# ModuleCarrier-Murata-ABZ-v1_0_0.net
KiCad netlist of a schematic drawn in EAGLE
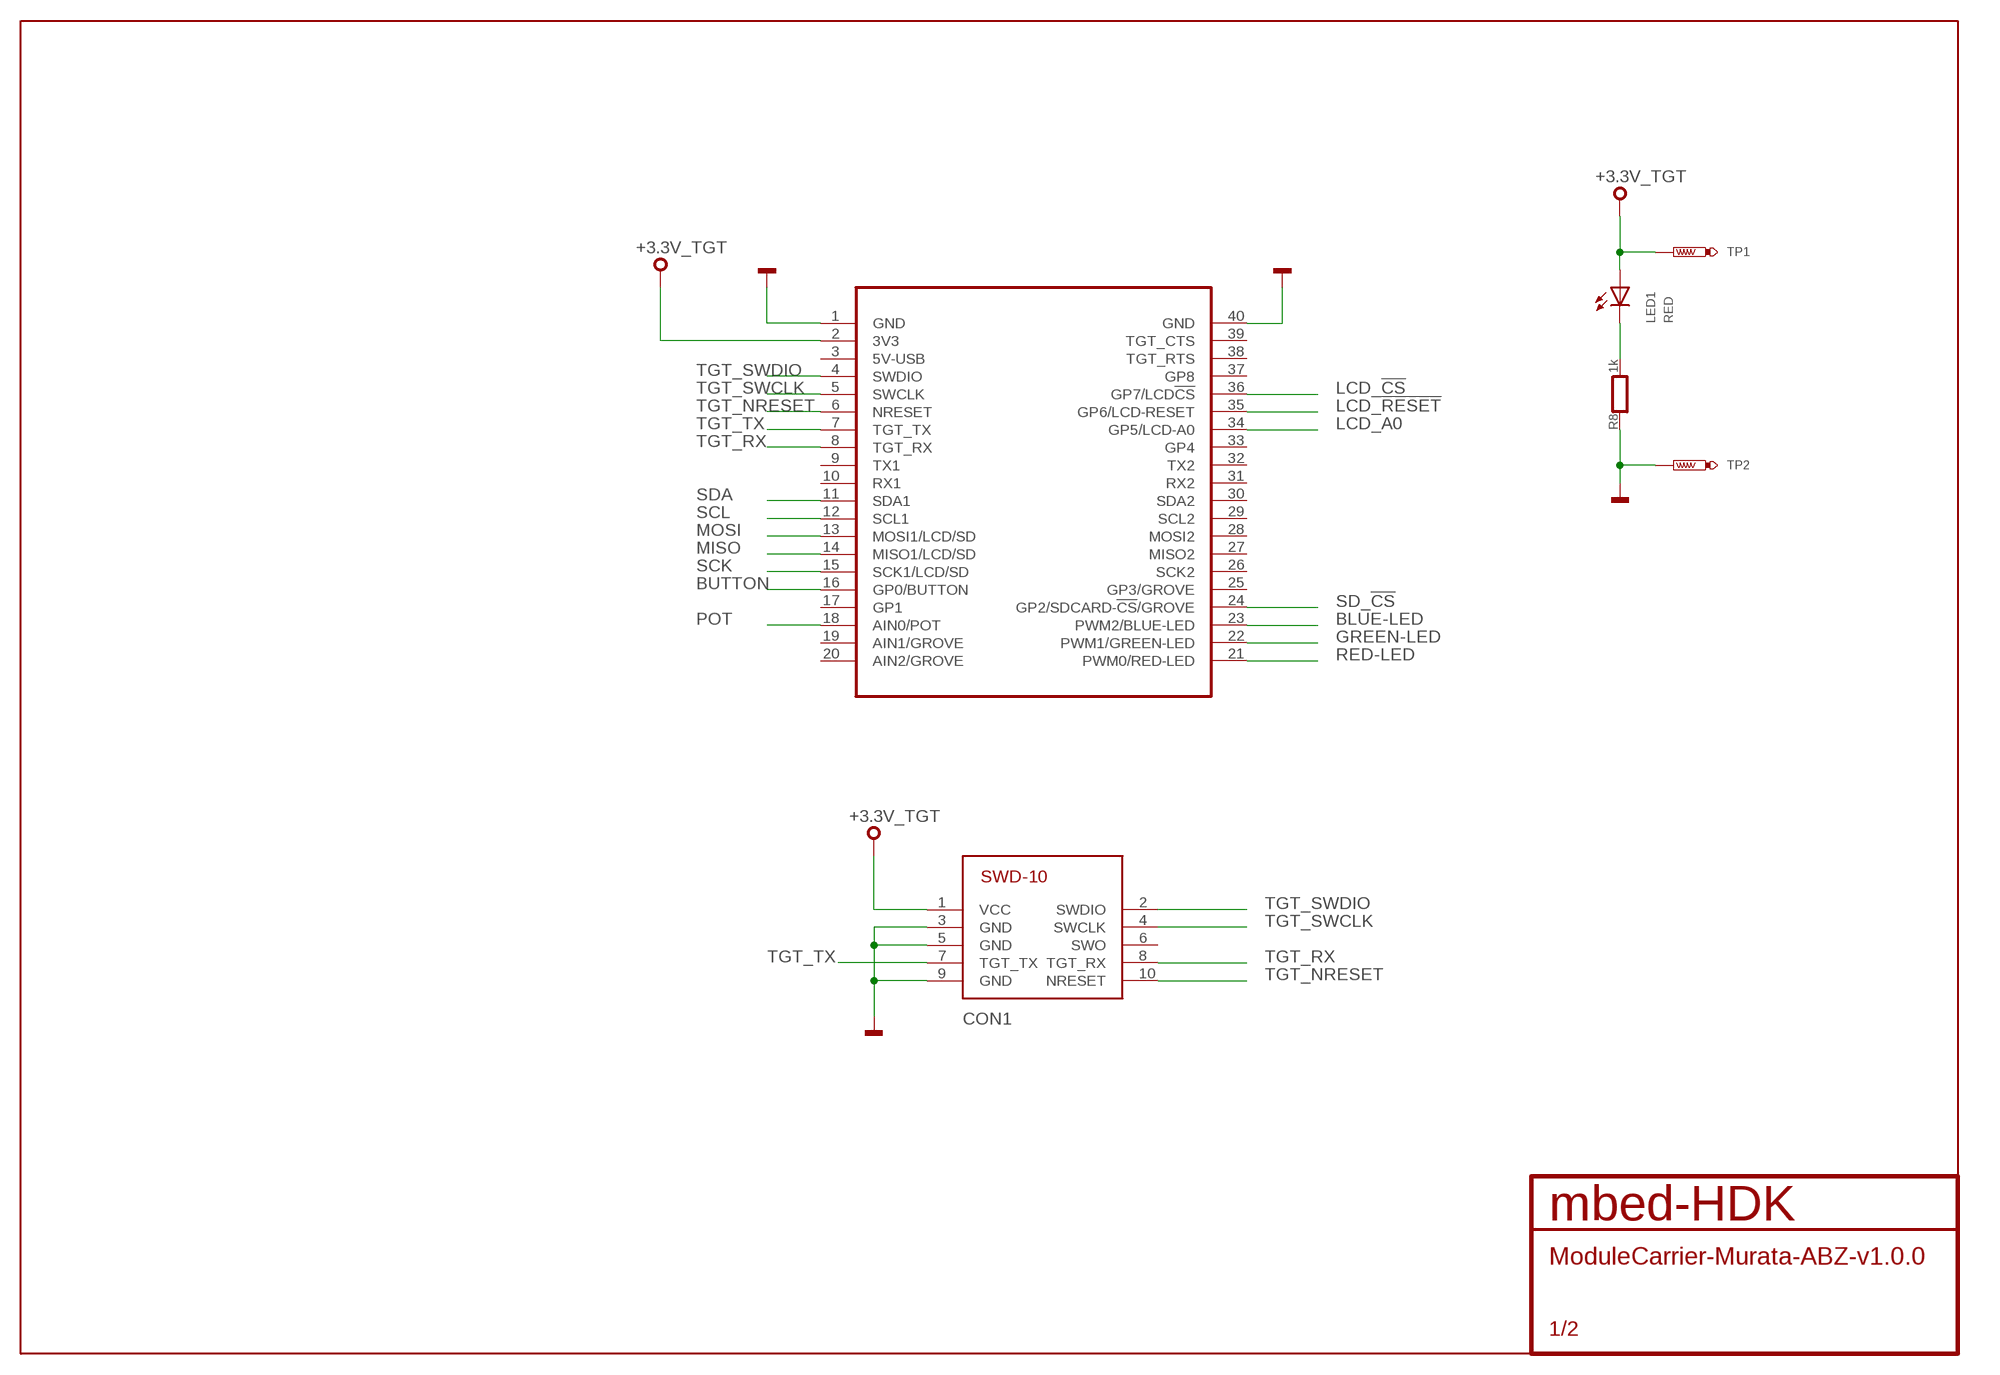
[diagram p0: schematic, sheet 1]
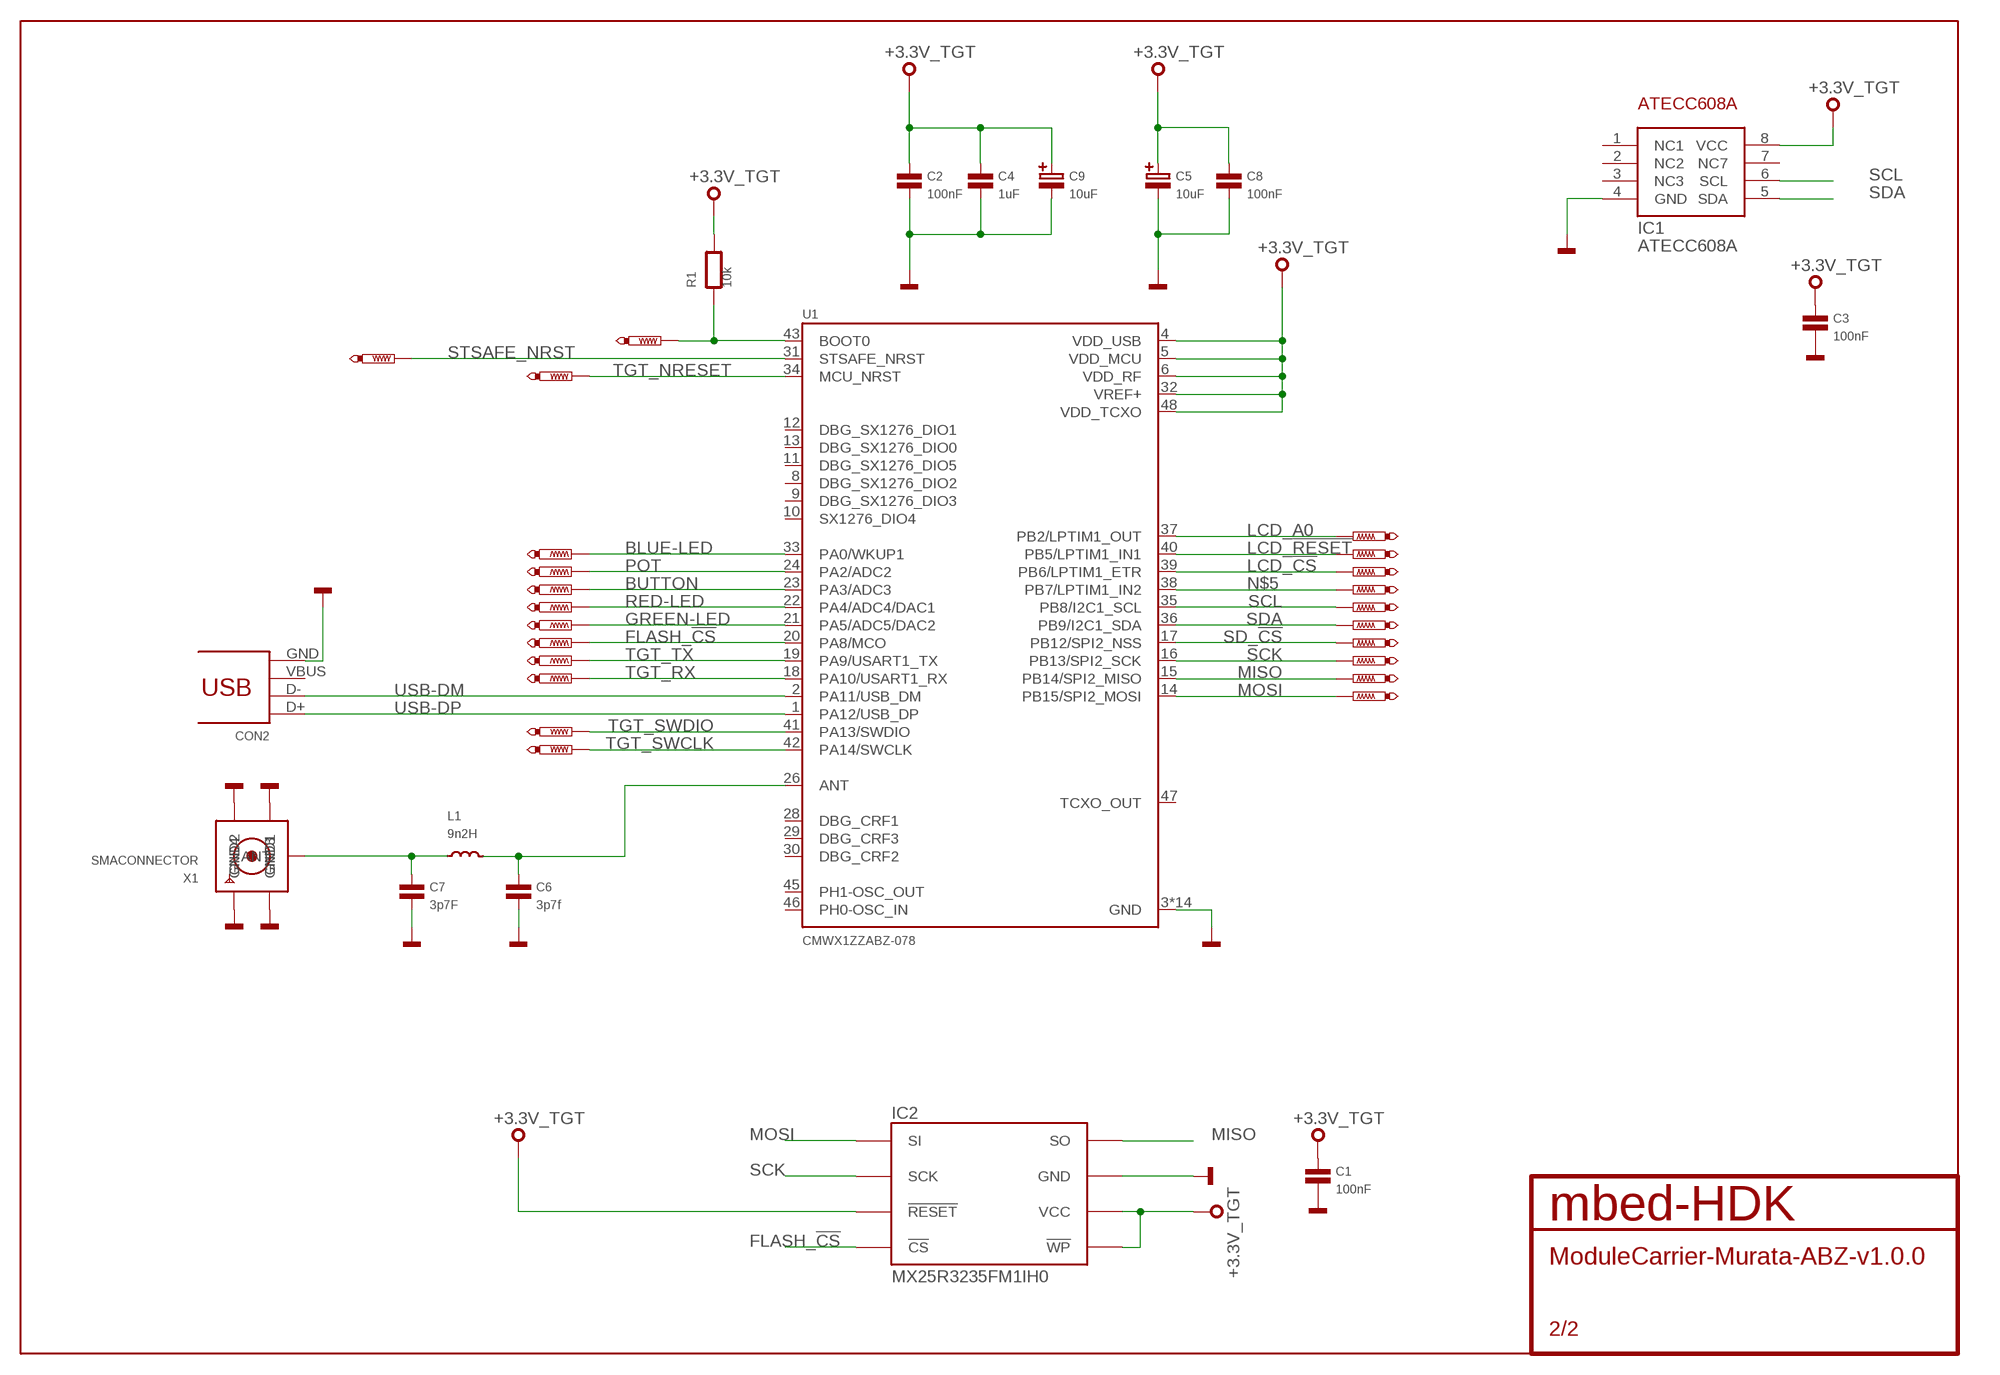
[diagram p1: schematic, sheet 2]

(export (version "E")
  (design (tool "Eeschema 10.0.6"))
  (components
    (comp (ref "C1")
      (value "100nF")
      (footprint "eagle-import:0603")
      (libsource (lib "eagle-import") (part "CAPACITOR0603"))
    )
    (comp (ref "C2")
      (value "100nF")
      (footprint "eagle-import:0603")
      (libsource (lib "eagle-import") (part "CAPACITOR0603"))
    )
    (comp (ref "C3")
      (value "100nF")
      (footprint "eagle-import:0603")
      (libsource (lib "eagle-import") (part "CAPACITOR0603"))
    )
    (comp (ref "C4")
      (value "1uF")
      (footprint "eagle-import:0603")
      (libsource (lib "eagle-import") (part "CAPACITOR0603"))
    )
    (comp (ref "C5")
      (value "10uF")
      (footprint "eagle-import:SMC_B")
      (fields (field (name "MF") "Kemet"))
      (libsource (lib "eagle-import") (part "CAPACITOR-POLARISEDB"))
    )
    (comp (ref "C6")
      (value "3p7f")
      (footprint "eagle-import:0603")
      (libsource (lib "eagle-import") (part "CAPACITOR0603"))
    )
    (comp (ref "C7")
      (value "3p7F")
      (footprint "eagle-import:0603")
      (libsource (lib "eagle-import") (part "CAPACITOR0603"))
    )
    (comp (ref "C8")
      (value "100nF")
      (footprint "eagle-import:0603")
      (libsource (lib "eagle-import") (part "CAPACITOR0603"))
    )
    (comp (ref "C9")
      (value "10uF")
      (footprint "eagle-import:SMC_B")
      (fields (field (name "MF") "Kemet"))
      (libsource (lib "eagle-import") (part "CAPACITOR-POLARISEDB"))
    )
    (comp (ref "CON2")
      (value "10033526-N3212MLF")
      (footprint "eagle-import:USB-MINI-B-H")
      (fields (field (name "MF") "Amphenol FCI"))
      (libsource (lib "eagle-import") (part "10033526-N3212MLF"))
    )
    (comp (ref "IC1")
      (value "ATECC608A")
      (footprint "eagle-import:SO8")
      (libsource (lib "eagle-import") (part "ATECC608A"))
    )
    (comp (ref "IC2")
      (value "MX25R3235FM1IH0")
      (footprint "eagle-import:SO8")
      (fields (field (name "MF") "Macronix"))
      (libsource (lib "eagle-import") (part "MX25R3235FM1IH0"))
    )
    (comp (ref "L1")
      (value "9n2H")
      (footprint "eagle-import:0603")
      (libsource (lib "eagle-import") (part "INDUCTOR0603"))
    )
    (comp (ref "R1")
      (value "10k")
      (footprint "eagle-import:0603")
      (libsource (lib "eagle-import") (part "RESISTOR0603"))
    )
    (comp (ref "TP3")
      (value "PTR1TP08R")
      (footprint "eagle-import:TP08R")
      (libsource (lib "eagle-import") (part "PTR1TP08R"))
    )
    (comp (ref "TP4")
      (value "PTR1TP08R")
      (footprint "eagle-import:TP08R")
      (libsource (lib "eagle-import") (part "PTR1TP08R"))
    )
    (comp (ref "TP5")
      (value "PTR1TP08R")
      (footprint "eagle-import:TP08R")
      (libsource (lib "eagle-import") (part "PTR1TP08R"))
    )
    (comp (ref "TP6")
      (value "PTR1TP08R")
      (footprint "eagle-import:TP08R")
      (libsource (lib "eagle-import") (part "PTR1TP08R"))
    )
    (comp (ref "TP7")
      (value "PTR1TP08R")
      (footprint "eagle-import:TP08R")
      (libsource (lib "eagle-import") (part "PTR1TP08R"))
    )
    (comp (ref "TP8")
      (value "PTR1TP08R")
      (footprint "eagle-import:TP08R")
      (libsource (lib "eagle-import") (part "PTR1TP08R"))
    )
    (comp (ref "TP9")
      (value "PTR1TP08R")
      (footprint "eagle-import:TP08R")
      (libsource (lib "eagle-import") (part "PTR1TP08R"))
    )
    (comp (ref "TP10")
      (value "PTR1TP08R")
      (footprint "eagle-import:TP08R")
      (libsource (lib "eagle-import") (part "PTR1TP08R"))
    )
    (comp (ref "TP11")
      (value "PTR1TP08R")
      (footprint "eagle-import:TP08R")
      (libsource (lib "eagle-import") (part "PTR1TP08R"))
    )
    (comp (ref "TP12")
      (value "PTR1TP08R")
      (footprint "eagle-import:TP08R")
      (libsource (lib "eagle-import") (part "PTR1TP08R"))
    )
    (comp (ref "TP13")
      (value "PTR1TP08R")
      (footprint "eagle-import:TP08R")
      (libsource (lib "eagle-import") (part "PTR1TP08R"))
    )
    (comp (ref "TP14")
      (value "PTR1TP08R")
      (footprint "eagle-import:TP08R")
      (libsource (lib "eagle-import") (part "PTR1TP08R"))
    )
    (comp (ref "TP15")
      (value "PTR1TP08R")
      (footprint "eagle-import:TP08R")
      (libsource (lib "eagle-import") (part "PTR1TP08R"))
    )
    (comp (ref "TP21")
      (value "PTR1TP08R")
      (footprint "eagle-import:TP08R")
      (libsource (lib "eagle-import") (part "PTR1TP08R"))
    )
    (comp (ref "TP22")
      (value "PTR1TP08R")
      (footprint "eagle-import:TP08R")
      (libsource (lib "eagle-import") (part "PTR1TP08R"))
    )
    (comp (ref "TP23")
      (value "PTR1TP08R")
      (footprint "eagle-import:TP08R")
      (libsource (lib "eagle-import") (part "PTR1TP08R"))
    )
    (comp (ref "TP24")
      (value "PTR1TP08R")
      (footprint "eagle-import:TP08R")
      (libsource (lib "eagle-import") (part "PTR1TP08R"))
    )
    (comp (ref "TP25")
      (value "PTR1TP08R")
      (footprint "eagle-import:TP08R")
      (libsource (lib "eagle-import") (part "PTR1TP08R"))
    )
    (comp (ref "TP26")
      (value "PTR1TP08R")
      (footprint "eagle-import:TP08R")
      (libsource (lib "eagle-import") (part "PTR1TP08R"))
    )
    (comp (ref "TP27")
      (value "PTR1TP08R")
      (footprint "eagle-import:TP08R")
      (libsource (lib "eagle-import") (part "PTR1TP08R"))
    )
    (comp (ref "TP28")
      (value "PTR1TP08R")
      (footprint "eagle-import:TP08R")
      (libsource (lib "eagle-import") (part "PTR1TP08R"))
    )
    (comp (ref "TP29")
      (value "PTR1TP08R")
      (footprint "eagle-import:TP08R")
      (libsource (lib "eagle-import") (part "PTR1TP08R"))
    )
    (comp (ref "TP30")
      (value "PTR1TP08R")
      (footprint "eagle-import:TP08R")
      (libsource (lib "eagle-import") (part "PTR1TP08R"))
    )
    (comp (ref "U1")
      (value "CMWX1ZZABZ-078")
      (footprint "eagle-import:XCVR_CMWX1ZZABZ-078")
      (fields (field (name "MF") "Murata"))
      (libsource (lib "eagle-import") (part "CMWX1ZZABZ-078"))
    )
    (comp (ref "X1")
      (value "SMACONNECTOR")
      (footprint "eagle-import:SMA90_DIP")
      (fields (field (name "MF") "LPRS") (field (name "MP") "SMA CONNECTOR"))
      (libsource (lib "eagle-import") (part "SMACONNECTOR"))
    )
    (comp (ref "CON1")
      (value "SWD-10/TC2050_SMD")
      (footprint "eagle-import:FTSH-105-02")
      (libsource (lib "eagle-import") (part "SWD-10/TC2050_SMD"))
    )
    (comp (ref "LED1")
      (value "RED")
      (footprint "eagle-import:CHIPLED_0603")
      (fields (field (name "MF") "Wurth Electronics Inc"))
      (libsource (lib "eagle-import") (part "SMD_LED0603"))
    )
    (comp (ref "MOD1")
      (value "MODULE_DAUGHTER")
      (footprint "eagle-import:MODULE_DAUGHTER")
      (libsource (lib "eagle-import") (part "MODULE_DAUGHTER"))
    )
    (comp (ref "R8")
      (value "1k")
      (footprint "eagle-import:0603")
      (libsource (lib "eagle-import") (part "RESISTOR0603"))
    )
    (comp (ref "TP1")
      (value "TEST-POINT-50R-PTH")
      (footprint "eagle-import:TP50-PTH")
      (libsource (lib "eagle-import") (part "TEST-POINT-50R-PTH"))
    )
    (comp (ref "TP2")
      (value "TEST-POINT-50R-PTH")
      (footprint "eagle-import:TP50-PTH")
      (libsource (lib "eagle-import") (part "TEST-POINT-50R-PTH"))
    )
  )
  (nets
    (net (code "1") (name "+3.3V_TGT") (class "Default")
      (node (ref "C1") (pin "1") (pinfunction "P$1_1") (pintype "passive"))
      (node (ref "C2") (pin "1") (pinfunction "P$1_1") (pintype "passive"))
      (node (ref "C3") (pin "1") (pinfunction "P$1_1") (pintype "passive"))
      (node (ref "C4") (pin "1") (pinfunction "P$1_1") (pintype "passive"))
      (node (ref "C5") (pin "+") (pinfunction "+_+") (pintype "passive"))
      (node (ref "C8") (pin "1") (pinfunction "P$1_1") (pintype "passive"))
      (node (ref "C9") (pin "+") (pinfunction "+_+") (pintype "passive"))
      (node (ref "CON1") (pin "1") (pinfunction "VCC_1") (pintype "bidirectional"))
      (node (ref "IC1") (pin "8") (pinfunction "VCC_8") (pintype "bidirectional"))
      (node (ref "IC2") (pin "3") (pinfunction "~{WP}_3") (pintype "bidirectional"))
      (node (ref "IC2") (pin "7") (pinfunction "~{RESET}_7") (pintype "bidirectional"))
      (node (ref "IC2") (pin "8") (pinfunction "VCC_8") (pintype "bidirectional"))
      (node (ref "LED1") (pin "A") (pinfunction "A_A") (pintype "passive"))
      (node (ref "MOD1") (pin "2") (pinfunction "3V3_2") (pintype "bidirectional"))
      (node (ref "R1") (pin "2") (pinfunction "P$2_2") (pintype "passive"))
      (node (ref "TP1") (pin "TP") (pinfunction "TP_TP") (pintype "input"))
      (node (ref "U1") (pin "32") (pinfunction "VREF+_32") (pintype "power_in"))
      (node (ref "U1") (pin "4") (pinfunction "VDD_USB_4") (pintype "power_in"))
      (node (ref "U1") (pin "48") (pinfunction "VDD_TCXO_48") (pintype "power_in"))
      (node (ref "U1") (pin "5") (pinfunction "VDD_MCU_5") (pintype "power_in"))
      (node (ref "U1") (pin "6") (pinfunction "VDD_RF_6") (pintype "power_in"))
    )
    (net (code "2") (name "BLUE-LED") (class "Default")
      (node (ref "MOD1") (pin "23") (pinfunction "PWM2/BLUE-LED_23") (pintype "bidirectional"))
      (node (ref "TP30") (pin "TP") (pinfunction "TP_TP") (pintype "input"))
      (node (ref "U1") (pin "33") (pinfunction "PA0/WKUP1_33") (pintype "bidirectional"))
    )
    (net (code "3") (name "BUTTON") (class "Default")
      (node (ref "MOD1") (pin "16") (pinfunction "GP0/BUTTON_16") (pintype "bidirectional"))
      (node (ref "TP11") (pin "TP") (pinfunction "TP_TP") (pintype "input"))
      (node (ref "U1") (pin "23") (pinfunction "PA3/ADC3_23") (pintype "bidirectional"))
    )
    (net (code "4") (name "FLASH_~{CS}") (class "Default")
      (node (ref "IC2") (pin "1") (pinfunction "~{CS}_1") (pintype "bidirectional"))
      (node (ref "TP29") (pin "TP") (pinfunction "TP_TP") (pintype "input"))
      (node (ref "U1") (pin "20") (pinfunction "PA8/MCO_20") (pintype "bidirectional"))
    )
    (net (code "5") (name "GND") (class "Default")
      (node (ref "C1") (pin "2") (pinfunction "P$2_2") (pintype "passive"))
      (node (ref "C2") (pin "2") (pinfunction "P$2_2") (pintype "passive"))
      (node (ref "C3") (pin "2") (pinfunction "P$2_2") (pintype "passive"))
      (node (ref "C4") (pin "2") (pinfunction "P$2_2") (pintype "passive"))
      (node (ref "C5") (pin "-") (pinfunction "-_-") (pintype "passive"))
      (node (ref "C6") (pin "2") (pinfunction "P$2_2") (pintype "passive"))
      (node (ref "C7") (pin "2") (pinfunction "P$2_2") (pintype "passive"))
      (node (ref "C8") (pin "2") (pinfunction "P$2_2") (pintype "passive"))
      (node (ref "C9") (pin "-") (pinfunction "-_-") (pintype "passive"))
      (node (ref "CON1") (pin "3") (pinfunction "GND_3") (pintype "bidirectional"))
      (node (ref "CON1") (pin "5") (pinfunction "GND_5") (pintype "bidirectional"))
      (node (ref "CON1") (pin "9") (pinfunction "GND_9") (pintype "bidirectional"))
      (node (ref "CON2") (pin "GND") (pinfunction "GND_GND") (pintype "bidirectional"))
      (node (ref "IC1") (pin "4") (pinfunction "GND_4") (pintype "bidirectional"))
      (node (ref "IC2") (pin "4") (pinfunction "GND_4") (pintype "bidirectional"))
      (node (ref "MOD1") (pin "1") (pinfunction "GND_1") (pintype "bidirectional"))
      (node (ref "MOD1") (pin "40") (pinfunction "GND_40") (pintype "bidirectional"))
      (node (ref "R8") (pin "1") (pinfunction "P$1_1") (pintype "passive"))
      (node (ref "TP2") (pin "TP") (pinfunction "TP_TP") (pintype "input"))
      (node (ref "U1") (pin "25") (pinfunction "GND_25") (pintype "power_in"))
      (node (ref "U1") (pin "27") (pinfunction "GND_27") (pintype "power_in"))
      (node (ref "U1") (pin "3") (pinfunction "GND_3") (pintype "power_in"))
      (node (ref "U1") (pin "44") (pinfunction "GND_44") (pintype "power_in"))
      (node (ref "U1") (pin "49") (pinfunction "GND_49") (pintype "power_in"))
      (node (ref "U1") (pin "50") (pinfunction "GND_50") (pintype "power_in"))
      (node (ref "U1") (pin "51") (pinfunction "GND_51") (pintype "power_in"))
      (node (ref "U1") (pin "52") (pinfunction "GND_52") (pintype "power_in"))
      (node (ref "U1") (pin "53") (pinfunction "GND_53") (pintype "power_in"))
      (node (ref "U1") (pin "54") (pinfunction "GND_54") (pintype "power_in"))
      (node (ref "U1") (pin "55") (pinfunction "GND_55") (pintype "power_in"))
      (node (ref "U1") (pin "56") (pinfunction "GND_56") (pintype "power_in"))
      (node (ref "U1") (pin "57") (pinfunction "GND_57") (pintype "power_in"))
      (node (ref "U1") (pin "7") (pinfunction "GND_7") (pintype "power_in"))
      (node (ref "X1") (pin "GND1") (pinfunction "GND1_GND1") (pintype "power_in"))
      (node (ref "X1") (pin "GND2") (pinfunction "GND2_GND2") (pintype "power_in"))
      (node (ref "X1") (pin "GND3") (pinfunction "GND3_GND3") (pintype "power_in"))
      (node (ref "X1") (pin "GND4") (pinfunction "GND4_GND4") (pintype "power_in"))
    )
    (net (code "6") (name "GREEN-LED") (class "Default")
      (node (ref "MOD1") (pin "22") (pinfunction "PWM1/GREEN-LED_22") (pintype "bidirectional"))
      (node (ref "TP28") (pin "TP") (pinfunction "TP_TP") (pintype "input"))
      (node (ref "U1") (pin "21") (pinfunction "PA5/ADC5/DAC2_21") (pintype "bidirectional"))
    )
    (net (code "7") (name "LCD_A0") (class "Default")
      (node (ref "MOD1") (pin "34") (pinfunction "GP5/LCD-A0_34") (pintype "bidirectional"))
      (node (ref "TP6") (pin "TP") (pinfunction "TP_TP") (pintype "input"))
      (node (ref "U1") (pin "37") (pinfunction "PB2/LPTIM1_OUT_37") (pintype "bidirectional"))
    )
    (net (code "8") (name "LCD_~{CS}") (class "Default")
      (node (ref "MOD1") (pin "36") (pinfunction "GP7/LCD~{CS}_36") (pintype "bidirectional"))
      (node (ref "TP25") (pin "TP") (pinfunction "TP_TP") (pintype "input"))
      (node (ref "U1") (pin "39") (pinfunction "PB6/LPTIM1_ETR_39") (pintype "bidirectional"))
    )
    (net (code "9") (name "LCD_~{RESET}") (class "Default")
      (node (ref "MOD1") (pin "35") (pinfunction "GP6/LCD-RESET_35") (pintype "bidirectional"))
      (node (ref "TP7") (pin "TP") (pinfunction "TP_TP") (pintype "input"))
      (node (ref "U1") (pin "40") (pinfunction "PB5/LPTIM1_IN1_40") (pintype "bidirectional"))
    )
    (net (code "10") (name "MISO") (class "Default")
      (node (ref "IC2") (pin "2") (pinfunction "SO_2") (pintype "bidirectional"))
      (node (ref "MOD1") (pin "14") (pinfunction "MISO1/LCD/SD_14") (pintype "bidirectional"))
      (node (ref "TP5") (pin "TP") (pinfunction "TP_TP") (pintype "input"))
      (node (ref "U1") (pin "15") (pinfunction "PB14/SPI2_MISO_15") (pintype "bidirectional"))
    )
    (net (code "11") (name "MOSI") (class "Default")
      (node (ref "IC2") (pin "5") (pinfunction "SI_5") (pintype "bidirectional"))
      (node (ref "MOD1") (pin "13") (pinfunction "MOSI1/LCD/SD_13") (pintype "bidirectional"))
      (node (ref "TP4") (pin "TP") (pinfunction "TP_TP") (pintype "input"))
      (node (ref "U1") (pin "14") (pinfunction "PB15/SPI2_MOSI_14") (pintype "bidirectional"))
    )
    (net (code "12") (name "N$5") (class "Default")
      (node (ref "TP26") (pin "TP") (pinfunction "TP_TP") (pintype "input"))
      (node (ref "U1") (pin "38") (pinfunction "PB7/LPTIM1_IN2_38") (pintype "bidirectional"))
    )
    (net (code "13") (name "Net-(C6-P$1)") (class "Default")
      (node (ref "C6") (pin "1") (pinfunction "P$1_1") (pintype "passive"))
      (node (ref "L1") (pin "2") (pinfunction "P$2_2") (pintype "bidirectional"))
      (node (ref "U1") (pin "26") (pinfunction "ANT_26") (pintype "bidirectional"))
    )
    (net (code "14") (name "Net-(C7-P$1)") (class "Default")
      (node (ref "C7") (pin "1") (pinfunction "P$1_1") (pintype "passive"))
      (node (ref "L1") (pin "1") (pinfunction "P$1_1") (pintype "bidirectional"))
      (node (ref "X1") (pin "ANTENNA") (pinfunction "ANT_ANTENNA") (pintype "bidirectional"))
    )
    (net (code "15") (name "Net-(R1-P$1)") (class "Default")
      (node (ref "R1") (pin "1") (pinfunction "P$1_1") (pintype "passive"))
      (node (ref "TP14") (pin "TP") (pinfunction "TP_TP") (pintype "input"))
      (node (ref "U1") (pin "43") (pinfunction "BOOT0_43") (pintype "input"))
    )
    (net (code "16") (name "Net-(R8-P$2)") (class "Default")
      (node (ref "LED1") (pin "C") (pinfunction "C_C") (pintype "passive"))
      (node (ref "R8") (pin "2") (pinfunction "P$2_2") (pintype "passive"))
    )
    (net (code "17") (name "POT") (class "Default")
      (node (ref "MOD1") (pin "18") (pinfunction "AIN0/POT_18") (pintype "bidirectional"))
      (node (ref "TP10") (pin "TP") (pinfunction "TP_TP") (pintype "input"))
      (node (ref "U1") (pin "24") (pinfunction "PA2/ADC2_24") (pintype "bidirectional"))
    )
    (net (code "18") (name "RED-LED") (class "Default")
      (node (ref "MOD1") (pin "21") (pinfunction "PWM0/RED-LED_21") (pintype "bidirectional"))
      (node (ref "TP24") (pin "TP") (pinfunction "TP_TP") (pintype "input"))
      (node (ref "U1") (pin "22") (pinfunction "PA4/ADC4/DAC1_22") (pintype "bidirectional"))
    )
    (net (code "19") (name "SCK") (class "Default")
      (node (ref "IC2") (pin "6") (pinfunction "SCK_6") (pintype "bidirectional"))
      (node (ref "MOD1") (pin "15") (pinfunction "SCK1/LCD/SD_15") (pintype "bidirectional"))
      (node (ref "TP3") (pin "TP") (pinfunction "TP_TP") (pintype "input"))
      (node (ref "U1") (pin "16") (pinfunction "PB13/SPI2_SCK_16") (pintype "bidirectional"))
    )
    (net (code "20") (name "SCL") (class "Default")
      (node (ref "IC1") (pin "6") (pinfunction "SCL_6") (pintype "bidirectional"))
      (node (ref "MOD1") (pin "12") (pinfunction "SCL1_12") (pintype "bidirectional"))
      (node (ref "TP12") (pin "TP") (pinfunction "TP_TP") (pintype "input"))
      (node (ref "U1") (pin "35") (pinfunction "PB8/I2C1_SCL_35") (pintype "bidirectional"))
    )
    (net (code "21") (name "SDA") (class "Default")
      (node (ref "IC1") (pin "5") (pinfunction "SDA_5") (pintype "bidirectional"))
      (node (ref "MOD1") (pin "11") (pinfunction "SDA1_11") (pintype "bidirectional"))
      (node (ref "TP13") (pin "TP") (pinfunction "TP_TP") (pintype "input"))
      (node (ref "U1") (pin "36") (pinfunction "PB9/I2C1_SDA_36") (pintype "bidirectional"))
    )
    (net (code "22") (name "SD_~{CS}") (class "Default")
      (node (ref "MOD1") (pin "24") (pinfunction "GP2/SDCARD-~{CS}/GROVE_24") (pintype "bidirectional"))
      (node (ref "TP27") (pin "TP") (pinfunction "TP_TP") (pintype "input"))
      (node (ref "U1") (pin "17") (pinfunction "PB12/SPI2_NSS_17") (pintype "bidirectional"))
    )
    (net (code "23") (name "STSAFE_NRST") (class "Default")
      (node (ref "TP15") (pin "TP") (pinfunction "TP_TP") (pintype "input"))
      (node (ref "U1") (pin "31") (pinfunction "STSAFE_NRST_31") (pintype "input"))
    )
    (net (code "24") (name "TGT_NRESET") (class "Default")
      (node (ref "CON1") (pin "10") (pinfunction "NRESET_10") (pintype "bidirectional"))
      (node (ref "MOD1") (pin "6") (pinfunction "NRESET_6") (pintype "bidirectional"))
      (node (ref "TP21") (pin "TP") (pinfunction "TP_TP") (pintype "input"))
      (node (ref "U1") (pin "34") (pinfunction "MCU_NRST_34") (pintype "input"))
    )
    (net (code "25") (name "TGT_RX") (class "Default")
      (node (ref "CON1") (pin "8") (pinfunction "TGT_RX_8") (pintype "bidirectional"))
      (node (ref "MOD1") (pin "8") (pinfunction "TGT_RX_8") (pintype "bidirectional"))
      (node (ref "TP9") (pin "TP") (pinfunction "TP_TP") (pintype "input"))
      (node (ref "U1") (pin "18") (pinfunction "PA10/USART1_RX_18") (pintype "bidirectional"))
    )
    (net (code "26") (name "TGT_SWCLK") (class "Default")
      (node (ref "CON1") (pin "4") (pinfunction "SWCLK_4") (pintype "bidirectional"))
      (node (ref "MOD1") (pin "5") (pinfunction "SWCLK_5") (pintype "bidirectional"))
      (node (ref "TP22") (pin "TP") (pinfunction "TP_TP") (pintype "input"))
      (node (ref "U1") (pin "42") (pinfunction "PA14/SWCLK_42") (pintype "bidirectional"))
    )
    (net (code "27") (name "TGT_SWDIO") (class "Default")
      (node (ref "CON1") (pin "2") (pinfunction "SWDIO_2") (pintype "bidirectional"))
      (node (ref "MOD1") (pin "4") (pinfunction "SWDIO_4") (pintype "bidirectional"))
      (node (ref "TP23") (pin "TP") (pinfunction "TP_TP") (pintype "input"))
      (node (ref "U1") (pin "41") (pinfunction "PA13/SWDIO_41") (pintype "bidirectional"))
    )
    (net (code "28") (name "TGT_TX") (class "Default")
      (node (ref "CON1") (pin "7") (pinfunction "TGT_TX_7") (pintype "bidirectional"))
      (node (ref "MOD1") (pin "7") (pinfunction "TGT_TX_7") (pintype "bidirectional"))
      (node (ref "TP8") (pin "TP") (pinfunction "TP_TP") (pintype "input"))
      (node (ref "U1") (pin "19") (pinfunction "PA9/USART1_TX_19") (pintype "bidirectional"))
    )
    (net (code "29") (name "USB-DM") (class "Default")
      (node (ref "CON2") (pin "D-") (pinfunction "D-_D-") (pintype "bidirectional"))
      (node (ref "U1") (pin "2") (pinfunction "PA11/USB_DM_2") (pintype "bidirectional"))
    )
    (net (code "30") (name "USB-DP") (class "Default")
      (node (ref "CON2") (pin "D+") (pinfunction "D+_D+") (pintype "bidirectional"))
      (node (ref "U1") (pin "1") (pinfunction "PA12/USB_DP_1") (pintype "bidirectional"))
    )
    (net (code "31") (name "unconnected-(CON1-SWO-Pad6)") (class "Default")
      (node (ref "CON1") (pin "6") (pinfunction "SWO_6") (pintype "bidirectional"))
    )
    (net (code "32") (name "unconnected-(CON2-PadVBUS)") (class "Default")
      (node (ref "CON2") (pin "VBUS") (pinfunction "VBUS_VBUS") (pintype "bidirectional"))
    )
    (net (code "33") (name "unconnected-(IC1-NC1-Pad1)") (class "Default")
      (node (ref "IC1") (pin "1") (pinfunction "NC1_1") (pintype "bidirectional"))
    )
    (net (code "34") (name "unconnected-(IC1-NC2-Pad2)") (class "Default")
      (node (ref "IC1") (pin "2") (pinfunction "NC2_2") (pintype "bidirectional"))
    )
    (net (code "35") (name "unconnected-(IC1-NC3-Pad3)") (class "Default")
      (node (ref "IC1") (pin "3") (pinfunction "NC3_3") (pintype "bidirectional"))
    )
    (net (code "36") (name "unconnected-(IC1-NC7-Pad7)") (class "Default")
      (node (ref "IC1") (pin "7") (pinfunction "NC7_7") (pintype "bidirectional"))
    )
    (net (code "37") (name "unconnected-(MOD1-5V-USB-Pad3)") (class "Default")
      (node (ref "MOD1") (pin "3") (pinfunction "5V-USB_3") (pintype "bidirectional"))
    )
    (net (code "38") (name "unconnected-(MOD1-AIN1{slash}GROVE-Pad19)") (class "Default")
      (node (ref "MOD1") (pin "19") (pinfunction "AIN1/GROVE_19") (pintype "bidirectional"))
    )
    (net (code "39") (name "unconnected-(MOD1-AIN2{slash}GROVE-Pad20)") (class "Default")
      (node (ref "MOD1") (pin "20") (pinfunction "AIN2/GROVE_20") (pintype "bidirectional"))
    )
    (net (code "40") (name "unconnected-(MOD1-GP1-Pad17)") (class "Default")
      (node (ref "MOD1") (pin "17") (pinfunction "GP1_17") (pintype "bidirectional"))
    )
    (net (code "41") (name "unconnected-(MOD1-GP3{slash}GROVE-Pad25)") (class "Default")
      (node (ref "MOD1") (pin "25") (pinfunction "GP3/GROVE_25") (pintype "bidirectional"))
    )
    (net (code "42") (name "unconnected-(MOD1-GP4-Pad33)") (class "Default")
      (node (ref "MOD1") (pin "33") (pinfunction "GP4_33") (pintype "bidirectional"))
    )
    (net (code "43") (name "unconnected-(MOD1-GP8-Pad37)") (class "Default")
      (node (ref "MOD1") (pin "37") (pinfunction "GP8_37") (pintype "bidirectional"))
    )
    (net (code "44") (name "unconnected-(MOD1-MISO2-Pad27)") (class "Default")
      (node (ref "MOD1") (pin "27") (pinfunction "MISO2_27") (pintype "bidirectional"))
    )
    (net (code "45") (name "unconnected-(MOD1-MOSI2-Pad28)") (class "Default")
      (node (ref "MOD1") (pin "28") (pinfunction "MOSI2_28") (pintype "bidirectional"))
    )
    (net (code "46") (name "unconnected-(MOD1-RX1-Pad10)") (class "Default")
      (node (ref "MOD1") (pin "10") (pinfunction "RX1_10") (pintype "bidirectional"))
    )
    (net (code "47") (name "unconnected-(MOD1-RX2-Pad31)") (class "Default")
      (node (ref "MOD1") (pin "31") (pinfunction "RX2_31") (pintype "bidirectional"))
    )
    (net (code "48") (name "unconnected-(MOD1-SCK2-Pad26)") (class "Default")
      (node (ref "MOD1") (pin "26") (pinfunction "SCK2_26") (pintype "bidirectional"))
    )
    (net (code "49") (name "unconnected-(MOD1-SCL2-Pad29)") (class "Default")
      (node (ref "MOD1") (pin "29") (pinfunction "SCL2_29") (pintype "bidirectional"))
    )
    (net (code "50") (name "unconnected-(MOD1-SDA2-Pad30)") (class "Default")
      (node (ref "MOD1") (pin "30") (pinfunction "SDA2_30") (pintype "bidirectional"))
    )
    (net (code "51") (name "unconnected-(MOD1-TGT_CTS-Pad39)") (class "Default")
      (node (ref "MOD1") (pin "39") (pinfunction "TGT_CTS_39") (pintype "bidirectional"))
    )
    (net (code "52") (name "unconnected-(MOD1-TGT_RTS-Pad38)") (class "Default")
      (node (ref "MOD1") (pin "38") (pinfunction "TGT_RTS_38") (pintype "bidirectional"))
    )
    (net (code "53") (name "unconnected-(MOD1-TX1-Pad9)") (class "Default")
      (node (ref "MOD1") (pin "9") (pinfunction "TX1_9") (pintype "bidirectional"))
    )
    (net (code "54") (name "unconnected-(MOD1-TX2-Pad32)") (class "Default")
      (node (ref "MOD1") (pin "32") (pinfunction "TX2_32") (pintype "bidirectional"))
    )
    (net (code "55") (name "unconnected-(U1-DBG_CRF1-Pad28)") (class "Default")
      (node (ref "U1") (pin "28") (pinfunction "DBG_CRF1_28") (pintype "bidirectional"))
    )
    (net (code "56") (name "unconnected-(U1-DBG_CRF2-Pad30)") (class "Default")
      (node (ref "U1") (pin "30") (pinfunction "DBG_CRF2_30") (pintype "bidirectional"))
    )
    (net (code "57") (name "unconnected-(U1-DBG_CRF3-Pad29)") (class "Default")
      (node (ref "U1") (pin "29") (pinfunction "DBG_CRF3_29") (pintype "bidirectional"))
    )
    (net (code "58") (name "unconnected-(U1-DBG_SX1276_DIO0-Pad13)") (class "Default")
      (node (ref "U1") (pin "13") (pinfunction "DBG_SX1276_DIO0_13") (pintype "bidirectional"))
    )
    (net (code "59") (name "unconnected-(U1-DBG_SX1276_DIO1-Pad12)") (class "Default")
      (node (ref "U1") (pin "12") (pinfunction "DBG_SX1276_DIO1_12") (pintype "bidirectional"))
    )
    (net (code "60") (name "unconnected-(U1-DBG_SX1276_DIO2-Pad8)") (class "Default")
      (node (ref "U1") (pin "8") (pinfunction "DBG_SX1276_DIO2_8") (pintype "bidirectional"))
    )
    (net (code "61") (name "unconnected-(U1-DBG_SX1276_DIO3-Pad9)") (class "Default")
      (node (ref "U1") (pin "9") (pinfunction "DBG_SX1276_DIO3_9") (pintype "bidirectional"))
    )
    (net (code "62") (name "unconnected-(U1-DBG_SX1276_DIO5-Pad11)") (class "Default")
      (node (ref "U1") (pin "11") (pinfunction "DBG_SX1276_DIO5_11") (pintype "bidirectional"))
    )
    (net (code "63") (name "unconnected-(U1-PH0-OSC_IN-Pad46)") (class "Default")
      (node (ref "U1") (pin "46") (pinfunction "PH0-OSC_IN_46") (pintype "bidirectional"))
    )
    (net (code "64") (name "unconnected-(U1-PH1-OSC_OUT-Pad45)") (class "Default")
      (node (ref "U1") (pin "45") (pinfunction "PH1-OSC_OUT_45") (pintype "bidirectional"))
    )
    (net (code "65") (name "unconnected-(U1-SX1276_DIO4-Pad10)") (class "Default")
      (node (ref "U1") (pin "10") (pinfunction "SX1276_DIO4_10") (pintype "bidirectional"))
    )
    (net (code "66") (name "unconnected-(U1-TCXO_OUT-Pad47)") (class "Default")
      (node (ref "U1") (pin "47") (pinfunction "TCXO_OUT_47") (pintype "output"))
    )
  )
)
